# amg8833.net
KiCad netlist of a schematic drawn in EAGLE
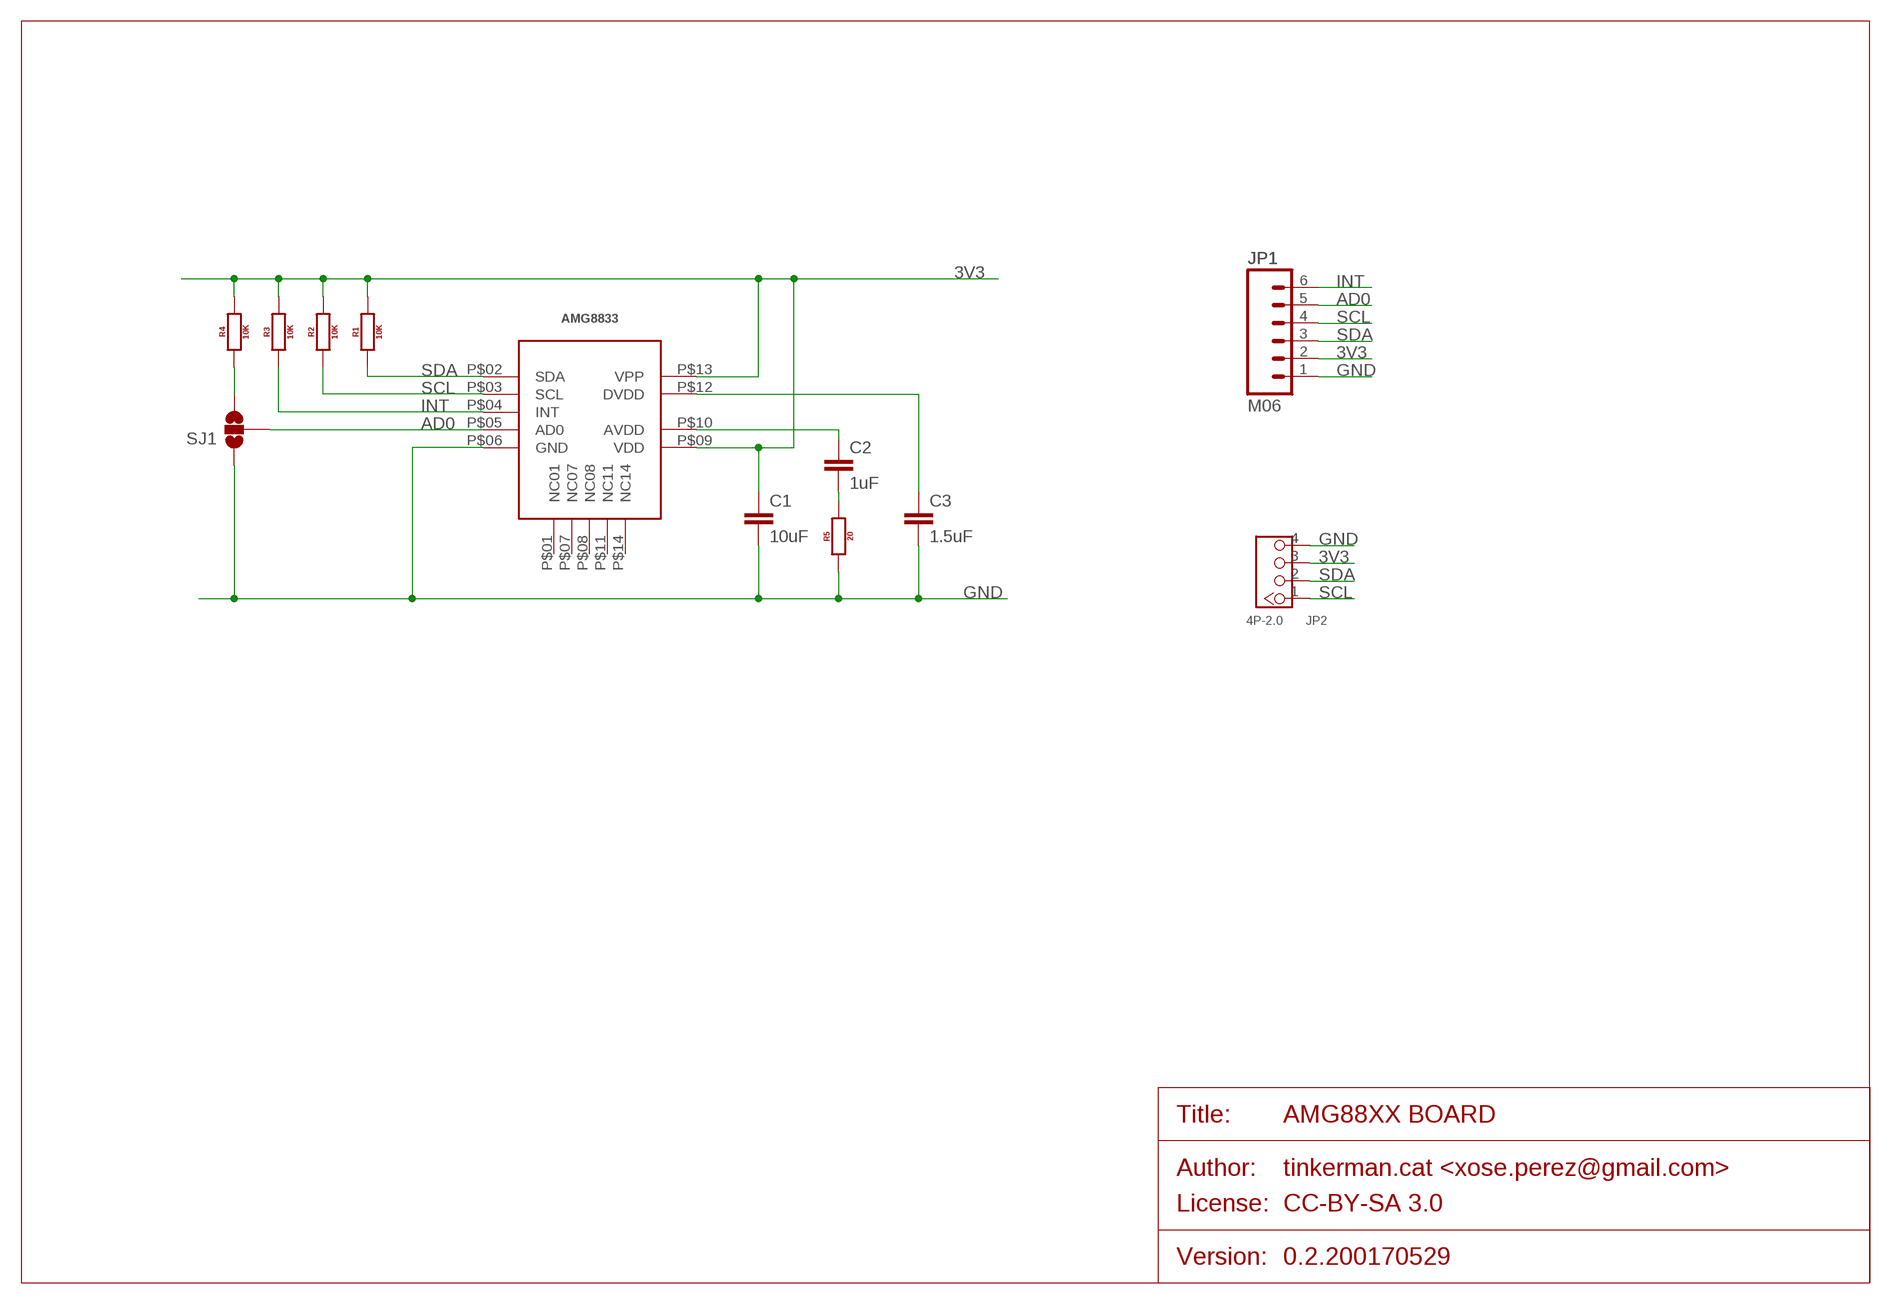
[diagram p0: schematic, sheet 1]

(export (version "E")
  (design (tool "Eeschema 10.0.6"))
  (components
    (comp (ref "AMG8833")
      (value "AMG88XX")
      (footprint "eagle-import:AMG88XX")
      (libsource (lib "eagle-import") (part "AMG88XX"))
    )
    (comp (ref "C1")
      (value "10uF")
      (footprint "eagle-import:0805")
      (libsource (lib "eagle-import") (part "C-EU0805"))
    )
    (comp (ref "C2")
      (value "1uF")
      (footprint "eagle-import:0805")
      (libsource (lib "eagle-import") (part "C-EU0805"))
    )
    (comp (ref "C3")
      (value "1.5uF")
      (footprint "eagle-import:0805")
      (libsource (lib "eagle-import") (part "C-EU0805"))
    )
    (comp (ref "JP1")
      (value "M06")
      (footprint "eagle-import:1X06_NO_SILK")
      (libsource (lib "eagle-import") (part "M06"))
    )
    (comp (ref "JP2")
      (value "4P-2.0")
      (footprint "eagle-import:HW4-2.0")
      (libsource (lib "eagle-import") (part "GROVE-CONNECTOR-DIP(4P-2.0)"))
    )
    (comp (ref "R1")
      (value "10K")
      (footprint "eagle-import:0805")
      (libsource (lib "eagle-import") (part "RESISTOR0805"))
    )
    (comp (ref "R2")
      (value "10K")
      (footprint "eagle-import:0805")
      (libsource (lib "eagle-import") (part "RESISTOR0805"))
    )
    (comp (ref "R3")
      (value "10K")
      (footprint "eagle-import:0805")
      (libsource (lib "eagle-import") (part "RESISTOR0805"))
    )
    (comp (ref "R4")
      (value "10K")
      (footprint "eagle-import:0805")
      (libsource (lib "eagle-import") (part "RESISTOR0805"))
    )
    (comp (ref "R5")
      (value "20")
      (footprint "eagle-import:0805")
      (libsource (lib "eagle-import") (part "RESISTOR0805"))
    )
    (comp (ref "SJ1")
      (value "SOLDERJUMPER_2WAYS")
      (footprint "eagle-import:SJ_3")
      (libsource (lib "eagle-import") (part "SOLDERJUMPER_2WAYS"))
    )
  )
  (nets
    (net (code "1") (name "/3V3") (class "Default")
      (node (ref "AMG8833") (pin "P$09") (pinfunction "VDD_P$09") (pintype "power_in"))
      (node (ref "AMG8833") (pin "P$13") (pinfunction "VPP_P$13") (pintype "power_in"))
      (node (ref "C1") (pin "1") (pinfunction "1_1") (pintype "passive"))
      (node (ref "JP1") (pin "2") (pinfunction "2_2") (pintype "passive"))
      (node (ref "JP2") (pin "3") (pinfunction "3_3") (pintype "bidirectional"))
      (node (ref "R1") (pin "2") (pinfunction "2_2") (pintype "passive"))
      (node (ref "R2") (pin "2") (pinfunction "2_2") (pintype "passive"))
      (node (ref "R3") (pin "2") (pinfunction "2_2") (pintype "passive"))
      (node (ref "R4") (pin "2") (pinfunction "2_2") (pintype "passive"))
    )
    (net (code "2") (name "/AD0") (class "Default")
      (node (ref "AMG8833") (pin "P$05") (pinfunction "AD0_P$05") (pintype "bidirectional"))
      (node (ref "JP1") (pin "5") (pinfunction "5_5") (pintype "passive"))
      (node (ref "SJ1") (pin "2") (pinfunction "2_2") (pintype "passive"))
    )
    (net (code "3") (name "/GND") (class "Default")
      (node (ref "AMG8833") (pin "P$06") (pinfunction "GND_P$06") (pintype "power_in"))
      (node (ref "C1") (pin "2") (pinfunction "2_2") (pintype "passive"))
      (node (ref "C3") (pin "2") (pinfunction "2_2") (pintype "passive"))
      (node (ref "JP1") (pin "1") (pinfunction "1_1") (pintype "passive"))
      (node (ref "JP2") (pin "4") (pinfunction "4_4") (pintype "bidirectional"))
      (node (ref "R5") (pin "1") (pinfunction "1_1") (pintype "passive"))
      (node (ref "SJ1") (pin "1") (pinfunction "1_1") (pintype "passive"))
    )
    (net (code "4") (name "/INT") (class "Default")
      (node (ref "AMG8833") (pin "P$04") (pinfunction "INT_P$04") (pintype "bidirectional"))
      (node (ref "JP1") (pin "6") (pinfunction "6_6") (pintype "passive"))
      (node (ref "R3") (pin "1") (pinfunction "1_1") (pintype "passive"))
    )
    (net (code "5") (name "/SCL") (class "Default")
      (node (ref "AMG8833") (pin "P$03") (pinfunction "SCL_P$03") (pintype "bidirectional"))
      (node (ref "JP1") (pin "4") (pinfunction "4_4") (pintype "passive"))
      (node (ref "JP2") (pin "1") (pinfunction "1_1") (pintype "bidirectional"))
      (node (ref "R2") (pin "1") (pinfunction "1_1") (pintype "passive"))
    )
    (net (code "6") (name "/SDA") (class "Default")
      (node (ref "AMG8833") (pin "P$02") (pinfunction "SDA_P$02") (pintype "bidirectional"))
      (node (ref "JP1") (pin "3") (pinfunction "3_3") (pintype "passive"))
      (node (ref "JP2") (pin "2") (pinfunction "2_2") (pintype "bidirectional"))
      (node (ref "R1") (pin "1") (pinfunction "1_1") (pintype "passive"))
    )
    (net (code "7") (name "Net-(AMG8833-AVDD)") (class "Default")
      (node (ref "AMG8833") (pin "P$10") (pinfunction "AVDD_P$10") (pintype "bidirectional"))
      (node (ref "C2") (pin "1") (pinfunction "1_1") (pintype "passive"))
    )
    (net (code "8") (name "Net-(AMG8833-DVDD)") (class "Default")
      (node (ref "AMG8833") (pin "P$12") (pinfunction "DVDD_P$12") (pintype "bidirectional"))
      (node (ref "C3") (pin "1") (pinfunction "1_1") (pintype "passive"))
    )
    (net (code "9") (name "Net-(C2-Pad2)") (class "Default")
      (node (ref "C2") (pin "2") (pinfunction "2_2") (pintype "passive"))
      (node (ref "R5") (pin "2") (pinfunction "2_2") (pintype "passive"))
    )
    (net (code "10") (name "Net-(R4-Pad1)") (class "Default")
      (node (ref "R4") (pin "1") (pinfunction "1_1") (pintype "passive"))
      (node (ref "SJ1") (pin "3") (pinfunction "3_3") (pintype "passive"))
    )
    (net (code "11") (name "unconnected-(AMG8833-NC01-PadP$01)") (class "Default")
      (node (ref "AMG8833") (pin "P$01") (pinfunction "NC01_P$01") (pintype "bidirectional"))
    )
    (net (code "12") (name "unconnected-(AMG8833-NC07-PadP$07)") (class "Default")
      (node (ref "AMG8833") (pin "P$07") (pinfunction "NC07_P$07") (pintype "bidirectional"))
    )
    (net (code "13") (name "unconnected-(AMG8833-NC08-PadP$08)") (class "Default")
      (node (ref "AMG8833") (pin "P$08") (pinfunction "NC08_P$08") (pintype "bidirectional"))
    )
    (net (code "14") (name "unconnected-(AMG8833-NC11-PadP$11)") (class "Default")
      (node (ref "AMG8833") (pin "P$11") (pinfunction "NC11_P$11") (pintype "bidirectional"))
    )
    (net (code "15") (name "unconnected-(AMG8833-NC14-PadP$14)") (class "Default")
      (node (ref "AMG8833") (pin "P$14") (pinfunction "NC14_P$14") (pintype "bidirectional"))
    )
  )
)
